# Sch_Phy.net
KiCad netlist of a schematic drawn in Altium Designer
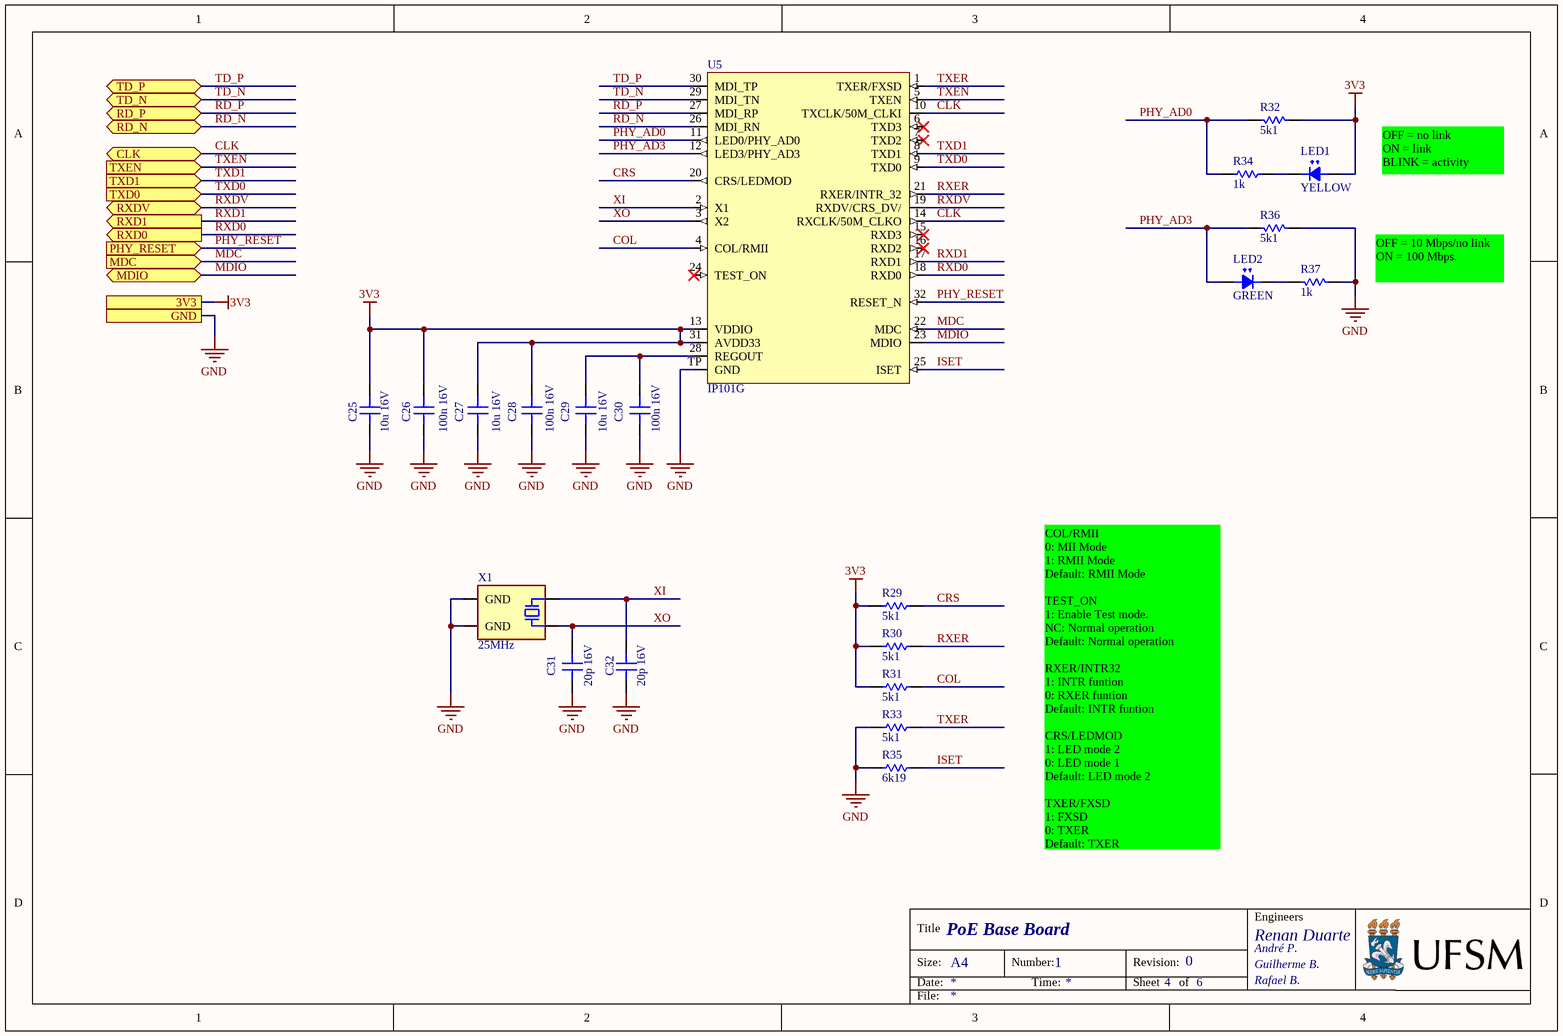
[diagram p0: Sch_Phy.SchDoc]

(export (version "E")
  (design (tool "Eeschema 10.0.6"))
  (components
    (comp (ref "C25")
      (value "10u 16V")
      (footprint "CAP_SMD_0603")
      (description "Capacitor SMD - Generic")
      (libsource (lib "AltiumLibrary") (part "CAP_SMD"))
    )
    (comp (ref "C26")
      (value "100n 16V")
      (footprint "CAP_SMD_0603")
      (description "Capacitor SMD - Generic")
      (libsource (lib "AltiumLibrary") (part "CAP_SMD"))
    )
    (comp (ref "C27")
      (value "10u 16V")
      (footprint "CAP_SMD_0603")
      (description "Capacitor SMD - Generic")
      (libsource (lib "AltiumLibrary") (part "CAP_SMD"))
    )
    (comp (ref "C28")
      (value "100n 16V")
      (footprint "CAP_SMD_0603")
      (description "Capacitor SMD - Generic")
      (libsource (lib "AltiumLibrary") (part "CAP_SMD"))
    )
    (comp (ref "C29")
      (value "10u 16V")
      (footprint "CAP_SMD_0603")
      (description "Capacitor SMD - Generic")
      (libsource (lib "AltiumLibrary") (part "CAP_SMD"))
    )
    (comp (ref "C30")
      (value "100n 16V")
      (footprint "CAP_SMD_0603")
      (description "Capacitor SMD - Generic")
      (libsource (lib "AltiumLibrary") (part "CAP_SMD"))
    )
    (comp (ref "C31")
      (value "20p 16V")
      (footprint "CAP_SMD_0603")
      (description "Capacitor SMD - Generic")
      (libsource (lib "AltiumLibrary") (part "CAP_SMD"))
    )
    (comp (ref "C32")
      (value "20p 16V")
      (footprint "CAP_SMD_0603")
      (description "Capacitor SMD - Generic")
      (libsource (lib "AltiumLibrary") (part "CAP_SMD"))
    )
    (comp (ref "LED1")
      (value "YELLOW")
      (footprint "LED_SMD_0603")
      (description "LED SMD - Generic")
      (libsource (lib "AltiumLibrary") (part "LED_SMD"))
    )
    (comp (ref "LED2")
      (value "GREEN")
      (footprint "LED_SMD_0603")
      (description "LED SMD - Generic")
      (libsource (lib "AltiumLibrary") (part "LED_SMD"))
    )
    (comp (ref "R29")
      (value "5k1")
      (footprint "RES_SMD_0603")
      (description "Resistor SMD - Generic")
      (libsource (lib "AltiumLibrary") (part "RES_SMD"))
    )
    (comp (ref "R30")
      (value "5k1")
      (footprint "RES_SMD_0603")
      (description "Resistor SMD - Generic")
      (libsource (lib "AltiumLibrary") (part "RES_SMD"))
    )
    (comp (ref "R31")
      (value "5k1")
      (footprint "RES_SMD_0603")
      (description "Resistor SMD - Generic")
      (libsource (lib "AltiumLibrary") (part "RES_SMD"))
    )
    (comp (ref "R32")
      (value "5k1")
      (footprint "RES_SMD_0603")
      (description "Resistor SMD - Generic")
      (libsource (lib "") (part "RES_SMD_1"))
    )
    (comp (ref "R33")
      (value "5k1")
      (footprint "RES_SMD_0603")
      (description "Resistor SMD - Generic")
      (libsource (lib "AltiumLibrary") (part "RES_SMD"))
    )
    (comp (ref "R34")
      (value "1k")
      (footprint "RES_SMD_0603")
      (description "Resistor SMD - Generic")
      (libsource (lib "AltiumLibrary") (part "RES_SMD"))
    )
    (comp (ref "R35")
      (value "6k19")
      (footprint "RES_SMD_0603")
      (description "Resistor SMD - Generic")
      (libsource (lib "AltiumLibrary") (part "RES_SMD"))
    )
    (comp (ref "R36")
      (value "5k1")
      (footprint "RES_SMD_0603")
      (description "Resistor SMD - Generic")
      (libsource (lib "") (part "RES_SMD_1"))
    )
    (comp (ref "R37")
      (value "1k")
      (footprint "RES_SMD_0603")
      (description "Resistor SMD - Generic")
      (libsource (lib "") (part "RES_SMD_1"))
    )
    (comp (ref "U5")
      (value "IP101G")
      (footprint "IC_QFN32_4x4")
      (description "Single Port 10/100 MII/RMII/TP/Fiber Fast Ethernet Transceiver")
      (libsource (lib "AltiumLibrary") (part "IC_IP101G"))
    )
    (comp (ref "X1")
      (value "25MHz")
      (footprint "XTAL_SMD_3525")
      (description "SMD Crystal with GND - Generic")
      (libsource (lib "AltiumLibrary") (part "XTAL_SMD_GND"))
    )
  )
  (nets
    (net (code "1") (name "/CLK") (class "Default")
      (node (ref "U5") (pin "10") (pinfunction "TXCLK/50M_CLKI_10") (pintype "bidirectional"))
      (node (ref "U5") (pin "14") (pinfunction "RXCLK/50M_CLKO_14") (pintype "output"))
    )
    (net (code "2") (name "/COL") (class "Default")
      (node (ref "R31") (pin "1") (pinfunction "1_1") (pintype "passive"))
      (node (ref "U5") (pin "4") (pinfunction "COL/RMII_4") (pintype "input"))
    )
    (net (code "3") (name "/CRS") (class "Default")
      (node (ref "R29") (pin "1") (pinfunction "1_1") (pintype "passive"))
      (node (ref "U5") (pin "20") (pinfunction "CRS/LEDMOD_20") (pintype "output"))
    )
    (net (code "4") (name "/ISET") (class "Default")
      (node (ref "R35") (pin "1") (pinfunction "1_1") (pintype "passive"))
      (node (ref "U5") (pin "25") (pinfunction "ISET_25") (pintype "input"))
    )
    (net (code "5") (name "/MDC") (class "Default")
      (node (ref "U5") (pin "22") (pinfunction "MDC_22") (pintype "input"))
    )
    (net (code "6") (name "/MDIO") (class "Default")
      (node (ref "U5") (pin "23") (pinfunction "MDIO_23") (pintype "bidirectional"))
    )
    (net (code "7") (name "/PHY_AD0") (class "Default")
      (node (ref "R32") (pin "1") (pinfunction "1_1") (pintype "passive"))
      (node (ref "R34") (pin "2") (pinfunction "2_2") (pintype "passive"))
      (node (ref "U5") (pin "11") (pinfunction "LED0/PHY_AD0_11") (pintype "output"))
    )
    (net (code "8") (name "/PHY_AD3") (class "Default")
      (node (ref "LED2") (pin "A") (pinfunction "A_A") (pintype "passive"))
      (node (ref "R36") (pin "1") (pinfunction "1_1") (pintype "passive"))
      (node (ref "U5") (pin "12") (pinfunction "LED3/PHY_AD3_12") (pintype "output"))
    )
    (net (code "9") (name "/PHY_RESET") (class "Default")
      (node (ref "U5") (pin "32") (pinfunction "RESET_N_32") (pintype "input"))
    )
    (net (code "10") (name "/RD_N") (class "Default")
      (node (ref "U5") (pin "26") (pinfunction "MDI_RN_26") (pintype "bidirectional"))
    )
    (net (code "11") (name "/RD_P") (class "Default")
      (node (ref "U5") (pin "27") (pinfunction "MDI_RP_27") (pintype "bidirectional"))
    )
    (net (code "12") (name "/RXD0") (class "Default")
      (node (ref "U5") (pin "18") (pinfunction "RXD0_18") (pintype "output"))
    )
    (net (code "13") (name "/RXD1") (class "Default")
      (node (ref "U5") (pin "17") (pinfunction "RXD1_17") (pintype "output"))
    )
    (net (code "14") (name "/RXDV") (class "Default")
      (node (ref "U5") (pin "19") (pinfunction "RXDV/CRS_DV/_19") (pintype "bidirectional"))
    )
    (net (code "15") (name "/RXER") (class "Default")
      (node (ref "R30") (pin "1") (pinfunction "1_1") (pintype "passive"))
      (node (ref "U5") (pin "21") (pinfunction "RXER/INTR_32_21") (pintype "output"))
    )
    (net (code "16") (name "/TD_N") (class "Default")
      (node (ref "U5") (pin "29") (pinfunction "MDI_TN_29") (pintype "bidirectional"))
    )
    (net (code "17") (name "/TD_P") (class "Default")
      (node (ref "U5") (pin "30") (pinfunction "MDI_TP_30") (pintype "bidirectional"))
    )
    (net (code "18") (name "/TXD0") (class "Default")
      (node (ref "U5") (pin "9") (pinfunction "TXD0_9") (pintype "input"))
    )
    (net (code "19") (name "/TXD1") (class "Default")
      (node (ref "U5") (pin "8") (pinfunction "TXD1_8") (pintype "input"))
    )
    (net (code "20") (name "/TXEN") (class "Default")
      (node (ref "U5") (pin "5") (pinfunction "TXEN_5") (pintype "input"))
    )
    (net (code "21") (name "/TXER") (class "Default")
      (node (ref "R33") (pin "1") (pinfunction "1_1") (pintype "passive"))
      (node (ref "U5") (pin "1") (pinfunction "TXER/FXSD_1") (pintype "input"))
    )
    (net (code "22") (name "/XI") (class "Default")
      (node (ref "C32") (pin "1") (pinfunction "1_1") (pintype "passive"))
      (node (ref "U5") (pin "2") (pinfunction "X1_2") (pintype "input"))
      (node (ref "X1") (pin "3") (pinfunction "3_3") (pintype "passive"))
    )
    (net (code "23") (name "/XO") (class "Default")
      (node (ref "C31") (pin "1") (pinfunction "1_1") (pintype "passive"))
      (node (ref "U5") (pin "3") (pinfunction "X2_3") (pintype "output"))
      (node (ref "X1") (pin "1") (pinfunction "1_1") (pintype "passive"))
    )
    (net (code "24") (name "3V3") (class "Default")
      (node (ref "C25") (pin "1") (pinfunction "1_1") (pintype "passive"))
      (node (ref "C26") (pin "1") (pinfunction "1_1") (pintype "passive"))
      (node (ref "C27") (pin "1") (pinfunction "1_1") (pintype "passive"))
      (node (ref "C28") (pin "1") (pinfunction "1_1") (pintype "passive"))
      (node (ref "LED1") (pin "A") (pinfunction "A_A") (pintype "passive"))
      (node (ref "R29") (pin "2") (pinfunction "2_2") (pintype "passive"))
      (node (ref "R30") (pin "2") (pinfunction "2_2") (pintype "passive"))
      (node (ref "R31") (pin "2") (pinfunction "2_2") (pintype "passive"))
      (node (ref "R32") (pin "2") (pinfunction "2_2") (pintype "passive"))
      (node (ref "U5") (pin "13") (pinfunction "VDDIO_13") (pintype "passive"))
      (node (ref "U5") (pin "31") (pinfunction "AVDD33_31") (pintype "passive"))
    )
    (net (code "25") (name "GND") (class "Default")
      (node (ref "C25") (pin "2") (pinfunction "2_2") (pintype "passive"))
      (node (ref "C26") (pin "2") (pinfunction "2_2") (pintype "passive"))
      (node (ref "C27") (pin "2") (pinfunction "2_2") (pintype "passive"))
      (node (ref "C28") (pin "2") (pinfunction "2_2") (pintype "passive"))
      (node (ref "C29") (pin "2") (pinfunction "2_2") (pintype "passive"))
      (node (ref "C30") (pin "2") (pinfunction "2_2") (pintype "passive"))
      (node (ref "C31") (pin "2") (pinfunction "2_2") (pintype "passive"))
      (node (ref "C32") (pin "2") (pinfunction "2_2") (pintype "passive"))
      (node (ref "R33") (pin "2") (pinfunction "2_2") (pintype "passive"))
      (node (ref "R35") (pin "2") (pinfunction "2_2") (pintype "passive"))
      (node (ref "R36") (pin "2") (pinfunction "2_2") (pintype "passive"))
      (node (ref "R37") (pin "2") (pinfunction "2_2") (pintype "passive"))
      (node (ref "U5") (pin "TP") (pinfunction "GND_TP") (pintype "passive"))
      (node (ref "X1") (pin "2") (pinfunction "GND_2") (pintype "passive"))
      (node (ref "X1") (pin "4") (pinfunction "GND_4") (pintype "passive"))
    )
    (net (code "26") (name "Net-(LED1-PadK)") (class "Default")
      (node (ref "LED1") (pin "K") (pinfunction "K_K") (pintype "passive"))
      (node (ref "R34") (pin "1") (pinfunction "1_1") (pintype "passive"))
    )
    (net (code "27") (name "Net-(LED2-PadK)") (class "Default")
      (node (ref "LED2") (pin "K") (pinfunction "K_K") (pintype "passive"))
      (node (ref "R37") (pin "1") (pinfunction "1_1") (pintype "passive"))
    )
    (net (code "28") (name "Net-(U5-REGOUT)") (class "Default")
      (node (ref "C29") (pin "1") (pinfunction "1_1") (pintype "passive"))
      (node (ref "C30") (pin "1") (pinfunction "1_1") (pintype "passive"))
      (node (ref "U5") (pin "28") (pinfunction "REGOUT_28") (pintype "passive"))
    )
    (net (code "29") (name "unconnected-(U5-RXD2-Pad16)") (class "Default")
      (node (ref "U5") (pin "16") (pinfunction "RXD2_16") (pintype "output+no_connect"))
    )
    (net (code "30") (name "unconnected-(U5-RXD3-Pad15)") (class "Default")
      (node (ref "U5") (pin "15") (pinfunction "RXD3_15") (pintype "output+no_connect"))
    )
    (net (code "31") (name "unconnected-(U5-TEST_ON-Pad24)") (class "Default")
      (node (ref "U5") (pin "24") (pinfunction "TEST_ON_24") (pintype "input+no_connect"))
    )
    (net (code "32") (name "unconnected-(U5-TXD2-Pad7)") (class "Default")
      (node (ref "U5") (pin "7") (pinfunction "TXD2_7") (pintype "input+no_connect"))
    )
    (net (code "33") (name "unconnected-(U5-TXD3-Pad6)") (class "Default")
      (node (ref "U5") (pin "6") (pinfunction "TXD3_6") (pintype "input+no_connect"))
    )
  )
)
